# MODULO_1_RELE.net
KiCad netlist of a schematic drawn in EAGLE
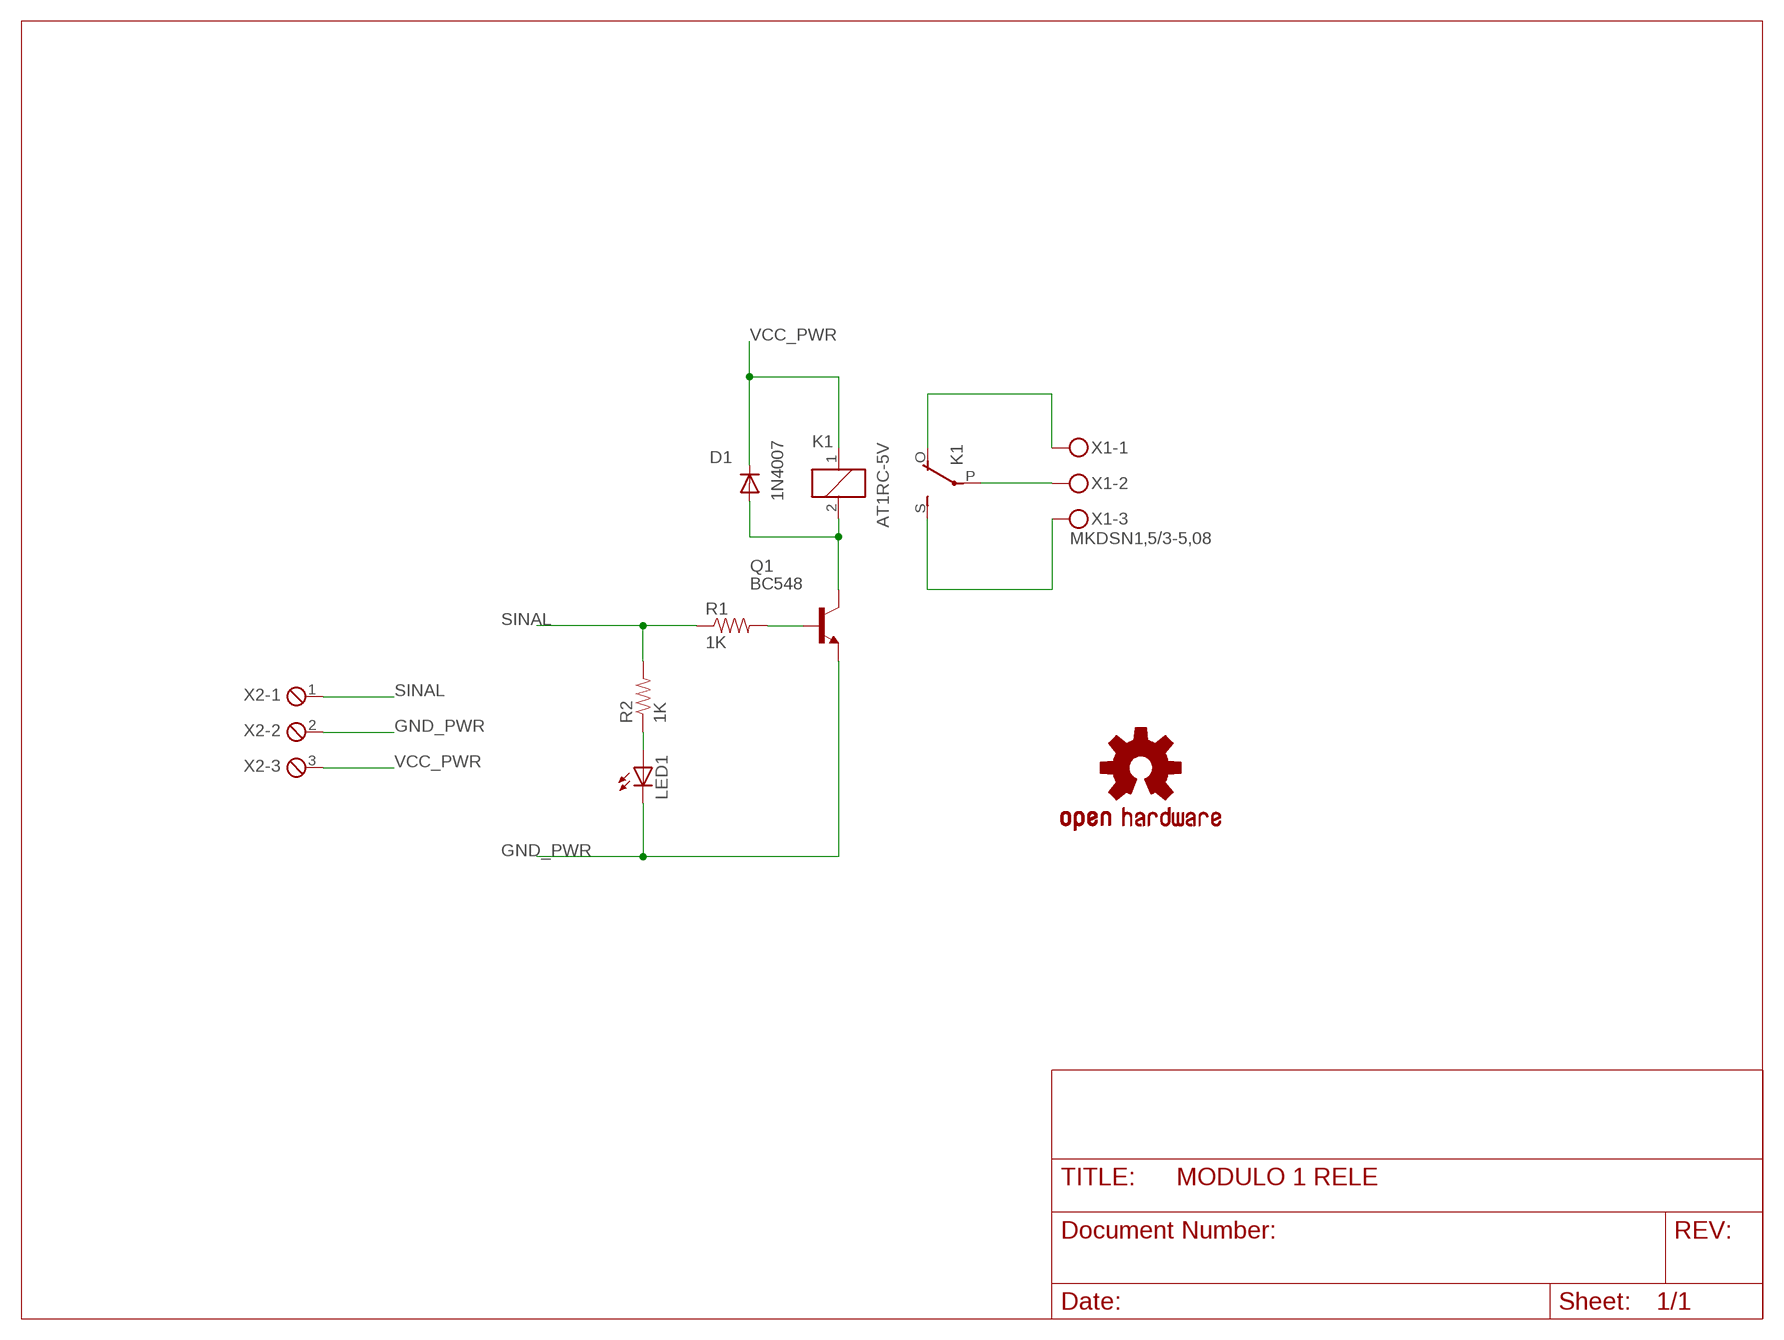
[diagram p0: schematic, sheet 1]

(export (version "E")
  (design (tool "Eeschema 10.0.6"))
  (components
    (comp (ref "D1")
      (value "1N4007")
      (footprint "eagle-import:DIODE-1N4001")
      (libsource (lib "eagle-import") (part "DIODEPTH"))
    )
    (comp (ref "K1")
      (value "AT1RC-5V")
      (footprint "eagle-import:G5LE")
      (libsource (lib "eagle-import") (part "G5L"))
    )
    (comp (ref "LED1")
      (value "LED3MM")
      (footprint "eagle-import:LED3MM")
      (libsource (lib "eagle-import") (part "LED3MM"))
    )
    (comp (ref "LOGO1")
      (value "OSHW-LOGOM")
      (footprint "eagle-import:OSHW-LOGO-M")
      (libsource (lib "eagle-import") (part "OSHW-LOGOM"))
    )
    (comp (ref "Q1")
      (value "BC548")
      (footprint "eagle-import:TO92-EBC")
      (libsource (lib "eagle-import") (part "BC548"))
    )
    (comp (ref "R1")
      (value "1K")
      (footprint "eagle-import:AXIAL-0.4")
      (libsource (lib "eagle-import") (part "RESISTORPTH-1/4W"))
    )
    (comp (ref "R2")
      (value "1K")
      (footprint "eagle-import:AXIAL-0.4")
      (libsource (lib "eagle-import") (part "RESISTORPTH-1/4W"))
    )
    (comp (ref "X1")
      (value "MKDSN1,5/3-5,08")
      (footprint "eagle-import:MKDSN1,5_3-5,08")
      (fields (field (name "MPN") "SMKDSN1,5/3-5,08"))
      (libsource (lib "eagle-import") (part "MKDSN1,5/3-5,08"))
    )
    (comp (ref "X2")
      (value "MPT3")
      (footprint "eagle-import:3POL254")
      (libsource (lib "eagle-import") (part "MPT3"))
    )
  )
  (nets
    (net (code "1") (name "/GND_PWR") (class "Default")
      (node (ref "LED1") (pin "K") (pinfunction "C_K") (pintype "passive"))
      (node (ref "Q1") (pin "E") (pinfunction "E_E") (pintype "passive"))
      (node (ref "X2") (pin "2") (pinfunction "1_2") (pintype "passive"))
    )
    (net (code "2") (name "/SINAL") (class "Default")
      (node (ref "R1") (pin "P$1") (pinfunction "1_P$1") (pintype "passive"))
      (node (ref "R2") (pin "P$2") (pinfunction "2_P$2") (pintype "passive"))
      (node (ref "X2") (pin "1") (pinfunction "1_1") (pintype "passive"))
    )
    (net (code "3") (name "/VCC_PWR") (class "Default")
      (node (ref "D1") (pin "C") (pinfunction "C_C") (pintype "passive"))
      (node (ref "K1") (pin "1") (pinfunction "1_1") (pintype "passive"))
      (node (ref "X2") (pin "3") (pinfunction "1_3") (pintype "passive"))
    )
    (net (code "4") (name "Net-(D1-PadA)") (class "Default")
      (node (ref "D1") (pin "A") (pinfunction "A_A") (pintype "passive"))
      (node (ref "K1") (pin "2") (pinfunction "2_2") (pintype "passive"))
      (node (ref "Q1") (pin "C") (pinfunction "C_C") (pintype "passive"))
    )
    (net (code "5") (name "Net-(R1-2)") (class "Default")
      (node (ref "Q1") (pin "B") (pinfunction "B_B") (pintype "passive"))
      (node (ref "R1") (pin "P$2") (pinfunction "2_P$2") (pintype "passive"))
    )
    (net (code "6") (name "Net-(R2-1)") (class "Default")
      (node (ref "LED1") (pin "A") (pinfunction "A_A") (pintype "passive"))
      (node (ref "R2") (pin "P$1") (pinfunction "1_P$1") (pintype "passive"))
    )
    (net (code "7") (name "Net-(X1A-KL)") (class "Default")
      (node (ref "K1") (pin "O") (pinfunction "O_O") (pintype "passive"))
      (node (ref "X1") (pin "1") (pinfunction "KL_1") (pintype "passive"))
    )
    (net (code "8") (name "Net-(X1B-KL)") (class "Default")
      (node (ref "K1") (pin "P") (pinfunction "P_P") (pintype "passive"))
      (node (ref "X1") (pin "2") (pinfunction "KL_2") (pintype "passive"))
    )
    (net (code "9") (name "Net-(X1C-KL)") (class "Default")
      (node (ref "K1") (pin "S") (pinfunction "S_S") (pintype "passive"))
      (node (ref "X1") (pin "3") (pinfunction "KL_3") (pintype "passive"))
    )
  )
)
